# stx_ra02.net
KiCad netlist of a schematic drawn in EAGLE
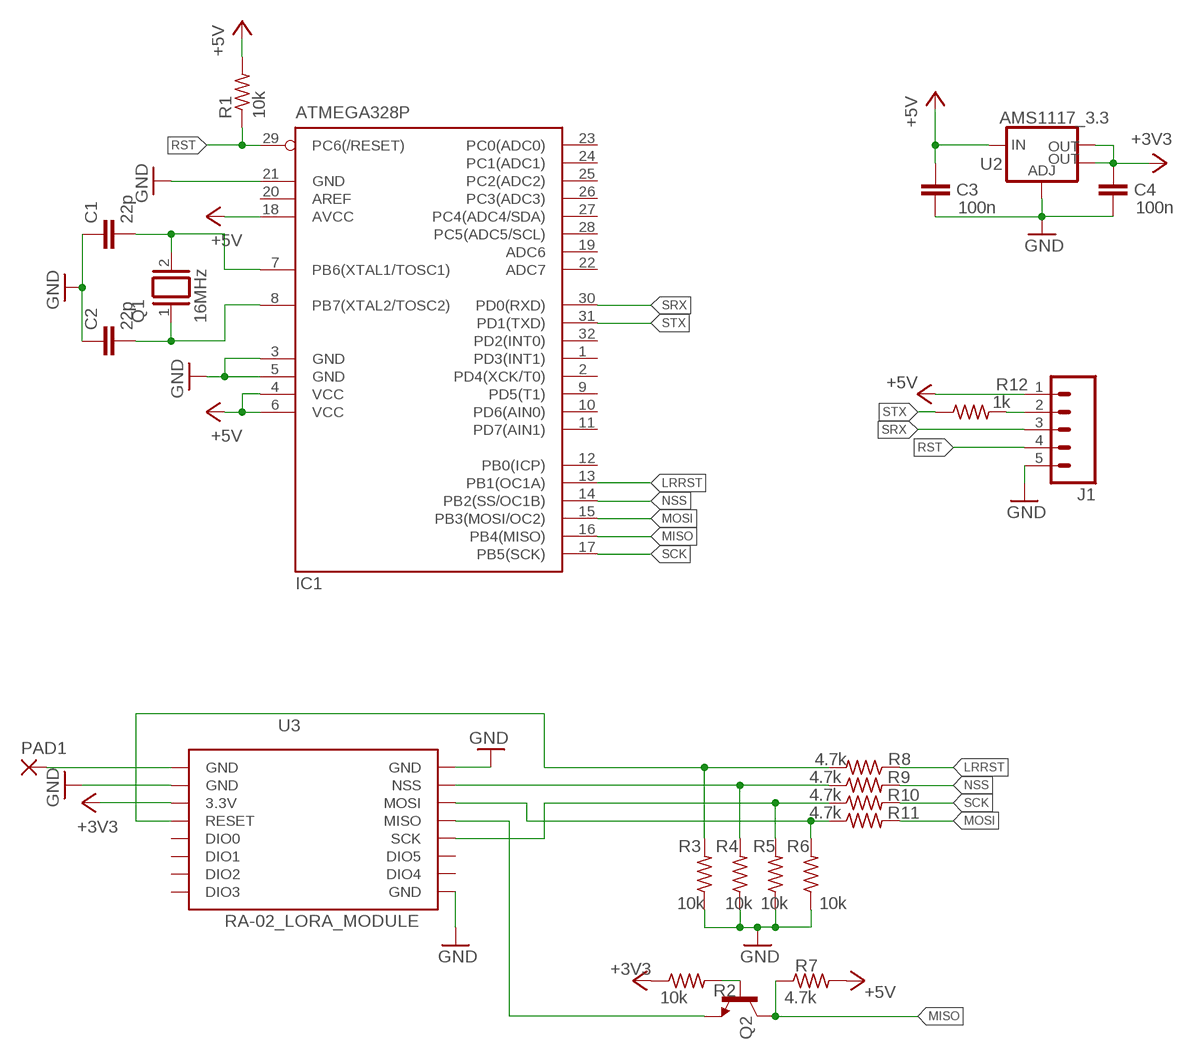
[diagram p0: schematic, sheet 1]

(export (version "E")
  (design (tool "Eeschema 10.0.6"))
  (components
    (comp (ref "C1")
      (value "22p")
      (footprint "eagle-import:C0805K")
      (libsource (lib "eagle-import") (part "C-EUC0805K"))
    )
    (comp (ref "C2")
      (value "22p")
      (footprint "eagle-import:C0805K")
      (libsource (lib "eagle-import") (part "C-EUC0805K"))
    )
    (comp (ref "C3")
      (value "100n")
      (footprint "eagle-import:C0805K")
      (libsource (lib "eagle-import") (part "C-EUC0805K"))
    )
    (comp (ref "C4")
      (value "100n")
      (footprint "eagle-import:C0805K")
      (libsource (lib "eagle-import") (part "C-EUC0805K"))
    )
    (comp (ref "IC1")
      (value "ATMEGA328P")
      (footprint "eagle-import:TQFP32-08")
      (fields (field (name "MPN") "ATMEGA8-16AU"))
      (libsource (lib "eagle-import") (part "MEGA8-AI"))
    )
    (comp (ref "J1")
      (value "M05PTH")
      (footprint "eagle-import:1X05")
      (libsource (lib "eagle-import") (part "M05PTH"))
    )
    (comp (ref "PAD1")
      (value "2,15/1,0")
      (footprint "eagle-import:2,15_1,0")
      (libsource (lib "eagle-import") (part "2,15/1,0"))
    )
    (comp (ref "Q1")
      (value "16MHz")
      (footprint "eagle-import:QS")
      (libsource (lib "eagle-import") (part "XTAL/S"))
    )
    (comp (ref "Q2")
      (value "BC817-16SMD")
      (footprint "eagle-import:SOT23-BEC")
      (libsource (lib "eagle-import") (part "BC817SMD-16"))
    )
    (comp (ref "R1")
      (value "10k")
      (footprint "eagle-import:R0805")
      (libsource (lib "eagle-import") (part "R-US_R0805"))
    )
    (comp (ref "R2")
      (value "10k")
      (footprint "eagle-import:R0805")
      (libsource (lib "eagle-import") (part "R-US_R0805"))
    )
    (comp (ref "R3")
      (value "10k")
      (footprint "eagle-import:R0805")
      (libsource (lib "eagle-import") (part "R-US_R0805"))
    )
    (comp (ref "R4")
      (value "10k")
      (footprint "eagle-import:R0805")
      (libsource (lib "eagle-import") (part "R-US_R0805"))
    )
    (comp (ref "R5")
      (value "10k")
      (footprint "eagle-import:R0805")
      (libsource (lib "eagle-import") (part "R-US_R0805"))
    )
    (comp (ref "R6")
      (value "10k")
      (footprint "eagle-import:R0805")
      (libsource (lib "eagle-import") (part "R-US_R0805"))
    )
    (comp (ref "R7")
      (value "4.7k")
      (footprint "eagle-import:R0805")
      (libsource (lib "eagle-import") (part "R-US_R0805"))
    )
    (comp (ref "R8")
      (value "4.7k")
      (footprint "eagle-import:R0805")
      (libsource (lib "eagle-import") (part "R-US_R0805"))
    )
    (comp (ref "R9")
      (value "4.7k")
      (footprint "eagle-import:R0805")
      (libsource (lib "eagle-import") (part "R-US_R0805"))
    )
    (comp (ref "R10")
      (value "4.7k")
      (footprint "eagle-import:R0805")
      (libsource (lib "eagle-import") (part "R-US_R0805"))
    )
    (comp (ref "R11")
      (value "4.7k")
      (footprint "eagle-import:R0805")
      (libsource (lib "eagle-import") (part "R-US_R0805"))
    )
    (comp (ref "R12")
      (value "1k")
      (footprint "eagle-import:R0805")
      (libsource (lib "eagle-import") (part "R-US_R0805"))
    )
    (comp (ref "U2")
      (value "AMS1117_3.3")
      (footprint "eagle-import:SOT223")
      (libsource (lib "eagle-import") (part "V_REG_LM1117SOT223"))
    )
    (comp (ref "U3")
      (value "RA-02_LORA_MODULE")
      (footprint "eagle-import:RA-02")
      (libsource (lib "eagle-import") (part "RA-02_LORA_MODULE"))
    )
  )
  (nets
    (net (code "1") (name "+3V3") (class "Default")
      (node (ref "C4") (pin "2") (pinfunction "2_2") (pintype "passive"))
      (node (ref "R2") (pin "1") (pinfunction "1_1") (pintype "passive"))
      (node (ref "U2") (pin "2") (pinfunction "OUT_2") (pintype "output"))
      (node (ref "U2") (pin "4") (pinfunction "OUT_4") (pintype "output"))
      (node (ref "U3") (pin "3.3V") (pinfunction "3.3V_3.3V") (pintype "power_in"))
    )
    (net (code "2") (name "+5V") (class "Default")
      (node (ref "C3") (pin "2") (pinfunction "2_2") (pintype "passive"))
      (node (ref "IC1") (pin "18") (pinfunction "AVCC_18") (pintype "power_in"))
      (node (ref "IC1") (pin "4") (pinfunction "VCC_4") (pintype "power_in"))
      (node (ref "IC1") (pin "6") (pinfunction "VCC_6") (pintype "power_in"))
      (node (ref "J1") (pin "1") (pinfunction "1_1") (pintype "passive"))
      (node (ref "R1") (pin "2") (pinfunction "2_2") (pintype "passive"))
      (node (ref "R7") (pin "2") (pinfunction "2_2") (pintype "passive"))
      (node (ref "U2") (pin "3") (pinfunction "IN_3") (pintype "input"))
    )
    (net (code "3") (name "GND") (class "Default")
      (node (ref "C1") (pin "1") (pinfunction "1_1") (pintype "passive"))
      (node (ref "C2") (pin "1") (pinfunction "1_1") (pintype "passive"))
      (node (ref "C3") (pin "1") (pinfunction "1_1") (pintype "passive"))
      (node (ref "C4") (pin "1") (pinfunction "1_1") (pintype "passive"))
      (node (ref "IC1") (pin "21") (pinfunction "GND_21") (pintype "power_in"))
      (node (ref "IC1") (pin "3") (pinfunction "GND_3") (pintype "power_in"))
      (node (ref "IC1") (pin "5") (pinfunction "GND_5") (pintype "power_in"))
      (node (ref "J1") (pin "5") (pinfunction "5_5") (pintype "passive"))
      (node (ref "R3") (pin "1") (pinfunction "1_1") (pintype "passive"))
      (node (ref "R4") (pin "1") (pinfunction "1_1") (pintype "passive"))
      (node (ref "R5") (pin "1") (pinfunction "1_1") (pintype "passive"))
      (node (ref "R6") (pin "1") (pinfunction "1_1") (pintype "passive"))
      (node (ref "U2") (pin "1") (pinfunction "ADJ_1") (pintype "input"))
      (node (ref "U3") (pin "GND@2") (pinfunction "GND_GND@2") (pintype "power_in"))
      (node (ref "U3") (pin "GND@3") (pinfunction "GND_GND@3") (pintype "power_in"))
      (node (ref "U3") (pin "GND@4") (pinfunction "GND_GND@4") (pintype "power_in"))
    )
    (net (code "4") (name "LRRST") (class "Default")
      (node (ref "IC1") (pin "13") (pinfunction "PB1(OC1A)_13") (pintype "bidirectional"))
      (node (ref "R8") (pin "1") (pinfunction "1_1") (pintype "passive"))
    )
    (net (code "5") (name "MISO") (class "Default")
      (node (ref "IC1") (pin "16") (pinfunction "PB4(MISO)_16") (pintype "bidirectional"))
      (node (ref "Q2") (pin "C") (pinfunction "C_C") (pintype "passive"))
      (node (ref "R7") (pin "1") (pinfunction "1_1") (pintype "passive"))
    )
    (net (code "6") (name "MOSI") (class "Default")
      (node (ref "IC1") (pin "15") (pinfunction "PB3(MOSI/OC2)_15") (pintype "bidirectional"))
      (node (ref "R11") (pin "2") (pinfunction "2_2") (pintype "passive"))
    )
    (net (code "7") (name "NSS") (class "Default")
      (node (ref "IC1") (pin "14") (pinfunction "PB2(SS/OC1B)_14") (pintype "bidirectional"))
      (node (ref "R9") (pin "2") (pinfunction "2_2") (pintype "passive"))
    )
    (net (code "8") (name "Net-(IC1-PB6(XTAL1{slash}TOSC1))") (class "Default")
      (node (ref "C1") (pin "2") (pinfunction "2_2") (pintype "passive"))
      (node (ref "IC1") (pin "7") (pinfunction "PB6(XTAL1/TOSC1)_7") (pintype "bidirectional"))
      (node (ref "Q1") (pin "2") (pinfunction "2_2") (pintype "passive"))
    )
    (net (code "9") (name "Net-(IC1-PB7(XTAL2{slash}TOSC2))") (class "Default")
      (node (ref "C2") (pin "2") (pinfunction "2_2") (pintype "passive"))
      (node (ref "IC1") (pin "8") (pinfunction "PB7(XTAL2/TOSC2)_8") (pintype "bidirectional"))
      (node (ref "Q1") (pin "1") (pinfunction "1_1") (pintype "passive"))
    )
    (net (code "10") (name "Net-(J1-Pad2)") (class "Default")
      (node (ref "J1") (pin "2") (pinfunction "2_2") (pintype "passive"))
      (node (ref "R12") (pin "2") (pinfunction "2_2") (pintype "passive"))
    )
    (net (code "11") (name "Net-(PAD1-P)") (class "Default")
      (node (ref "PAD1") (pin "1") (pinfunction "P_1") (pintype "passive"))
      (node (ref "U3") (pin "GND") (pinfunction "GND_GND") (pintype "power_in"))
    )
    (net (code "12") (name "Net-(Q2-PadB)") (class "Default")
      (node (ref "Q2") (pin "B") (pinfunction "B_B") (pintype "passive"))
      (node (ref "R2") (pin "2") (pinfunction "2_2") (pintype "passive"))
    )
    (net (code "13") (name "Net-(Q2-PadE)") (class "Default")
      (node (ref "Q2") (pin "E") (pinfunction "E_E") (pintype "passive"))
      (node (ref "U3") (pin "MISO") (pinfunction "MISO_MISO") (pintype "bidirectional"))
    )
    (net (code "14") (name "Net-(R3-Pad2)") (class "Default")
      (node (ref "R3") (pin "2") (pinfunction "2_2") (pintype "passive"))
      (node (ref "R8") (pin "2") (pinfunction "2_2") (pintype "passive"))
      (node (ref "U3") (pin "RESET") (pinfunction "RESET_RESET") (pintype "bidirectional"))
    )
    (net (code "15") (name "Net-(R4-Pad2)") (class "Default")
      (node (ref "R4") (pin "2") (pinfunction "2_2") (pintype "passive"))
      (node (ref "R9") (pin "1") (pinfunction "1_1") (pintype "passive"))
      (node (ref "U3") (pin "NSS") (pinfunction "NSS_NSS") (pintype "bidirectional"))
    )
    (net (code "16") (name "Net-(R10-Pad1)") (class "Default")
      (node (ref "R10") (pin "1") (pinfunction "1_1") (pintype "passive"))
      (node (ref "R5") (pin "2") (pinfunction "2_2") (pintype "passive"))
      (node (ref "U3") (pin "SCK") (pinfunction "SCK_SCK") (pintype "bidirectional"))
    )
    (net (code "17") (name "Net-(R11-Pad1)") (class "Default")
      (node (ref "R11") (pin "1") (pinfunction "1_1") (pintype "passive"))
      (node (ref "R6") (pin "2") (pinfunction "2_2") (pintype "passive"))
      (node (ref "U3") (pin "MOSI") (pinfunction "MOSI_MOSI") (pintype "bidirectional"))
    )
    (net (code "18") (name "RST") (class "Default")
      (node (ref "IC1") (pin "29") (pinfunction "PC6(/RESET)_29") (pintype "bidirectional"))
      (node (ref "J1") (pin "4") (pinfunction "4_4") (pintype "passive"))
      (node (ref "R1") (pin "1") (pinfunction "1_1") (pintype "passive"))
    )
    (net (code "19") (name "SCK") (class "Default")
      (node (ref "IC1") (pin "17") (pinfunction "PB5(SCK)_17") (pintype "bidirectional"))
      (node (ref "R10") (pin "2") (pinfunction "2_2") (pintype "passive"))
    )
    (net (code "20") (name "SRX") (class "Default")
      (node (ref "IC1") (pin "30") (pinfunction "PD0(RXD)_30") (pintype "bidirectional"))
      (node (ref "J1") (pin "3") (pinfunction "3_3") (pintype "passive"))
    )
    (net (code "21") (name "STX") (class "Default")
      (node (ref "IC1") (pin "31") (pinfunction "PD1(TXD)_31") (pintype "bidirectional"))
      (node (ref "R12") (pin "1") (pinfunction "1_1") (pintype "passive"))
    )
    (net (code "22") (name "unconnected-(IC1-ADC6-Pad19)") (class "Default")
      (node (ref "IC1") (pin "19") (pinfunction "ADC6_19") (pintype "bidirectional"))
    )
    (net (code "23") (name "unconnected-(IC1-ADC7-Pad22)") (class "Default")
      (node (ref "IC1") (pin "22") (pinfunction "ADC7_22") (pintype "bidirectional"))
    )
    (net (code "24") (name "unconnected-(IC1-AREF-Pad20)") (class "Default")
      (node (ref "IC1") (pin "20") (pinfunction "AREF_20") (pintype "passive"))
    )
    (net (code "25") (name "unconnected-(IC1-PB0(ICP)-Pad12)") (class "Default")
      (node (ref "IC1") (pin "12") (pinfunction "PB0(ICP)_12") (pintype "bidirectional"))
    )
    (net (code "26") (name "unconnected-(IC1-PC0(ADC0)-Pad23)") (class "Default")
      (node (ref "IC1") (pin "23") (pinfunction "PC0(ADC0)_23") (pintype "bidirectional"))
    )
    (net (code "27") (name "unconnected-(IC1-PC1(ADC1)-Pad24)") (class "Default")
      (node (ref "IC1") (pin "24") (pinfunction "PC1(ADC1)_24") (pintype "bidirectional"))
    )
    (net (code "28") (name "unconnected-(IC1-PC2(ADC2)-Pad25)") (class "Default")
      (node (ref "IC1") (pin "25") (pinfunction "PC2(ADC2)_25") (pintype "bidirectional"))
    )
    (net (code "29") (name "unconnected-(IC1-PC3(ADC3)-Pad26)") (class "Default")
      (node (ref "IC1") (pin "26") (pinfunction "PC3(ADC3)_26") (pintype "bidirectional"))
    )
    (net (code "30") (name "unconnected-(IC1-PC4(ADC4{slash}SDA)-Pad27)") (class "Default")
      (node (ref "IC1") (pin "27") (pinfunction "PC4(ADC4/SDA)_27") (pintype "bidirectional"))
    )
    (net (code "31") (name "unconnected-(IC1-PC5(ADC5{slash}SCL)-Pad28)") (class "Default")
      (node (ref "IC1") (pin "28") (pinfunction "PC5(ADC5/SCL)_28") (pintype "bidirectional"))
    )
    (net (code "32") (name "unconnected-(IC1-PD2(INT0)-Pad32)") (class "Default")
      (node (ref "IC1") (pin "32") (pinfunction "PD2(INT0)_32") (pintype "bidirectional"))
    )
    (net (code "33") (name "unconnected-(IC1-PD3(INT1)-Pad1)") (class "Default")
      (node (ref "IC1") (pin "1") (pinfunction "PD3(INT1)_1") (pintype "bidirectional"))
    )
    (net (code "34") (name "unconnected-(IC1-PD4(XCK{slash}T0)-Pad2)") (class "Default")
      (node (ref "IC1") (pin "2") (pinfunction "PD4(XCK/T0)_2") (pintype "bidirectional"))
    )
    (net (code "35") (name "unconnected-(IC1-PD5(T1)-Pad9)") (class "Default")
      (node (ref "IC1") (pin "9") (pinfunction "PD5(T1)_9") (pintype "bidirectional"))
    )
    (net (code "36") (name "unconnected-(IC1-PD6(AIN0)-Pad10)") (class "Default")
      (node (ref "IC1") (pin "10") (pinfunction "PD6(AIN0)_10") (pintype "bidirectional"))
    )
    (net (code "37") (name "unconnected-(IC1-PD7(AIN1)-Pad11)") (class "Default")
      (node (ref "IC1") (pin "11") (pinfunction "PD7(AIN1)_11") (pintype "bidirectional"))
    )
    (net (code "38") (name "unconnected-(U3-PadDIO0)") (class "Default")
      (node (ref "U3") (pin "DIO0") (pinfunction "DIO0_DIO0") (pintype "bidirectional"))
    )
    (net (code "39") (name "unconnected-(U3-PadDIO1)") (class "Default")
      (node (ref "U3") (pin "DIO1") (pinfunction "DIO1_DIO1") (pintype "bidirectional"))
    )
    (net (code "40") (name "unconnected-(U3-PadDIO2)") (class "Default")
      (node (ref "U3") (pin "DIO2") (pinfunction "DIO2_DIO2") (pintype "bidirectional"))
    )
    (net (code "41") (name "unconnected-(U3-PadDIO3)") (class "Default")
      (node (ref "U3") (pin "DIO3") (pinfunction "DIO3_DIO3") (pintype "bidirectional"))
    )
    (net (code "42") (name "unconnected-(U3-PadDIO4)") (class "Default")
      (node (ref "U3") (pin "DIO4") (pinfunction "DIO4_DIO4") (pintype "bidirectional"))
    )
    (net (code "43") (name "unconnected-(U3-PadDIO5)") (class "Default")
      (node (ref "U3") (pin "DIO5") (pinfunction "DIO5_DIO5") (pintype "bidirectional"))
    )
  )
)
